# Sheet1.net
KiCad netlist of a schematic drawn in Altium Designer
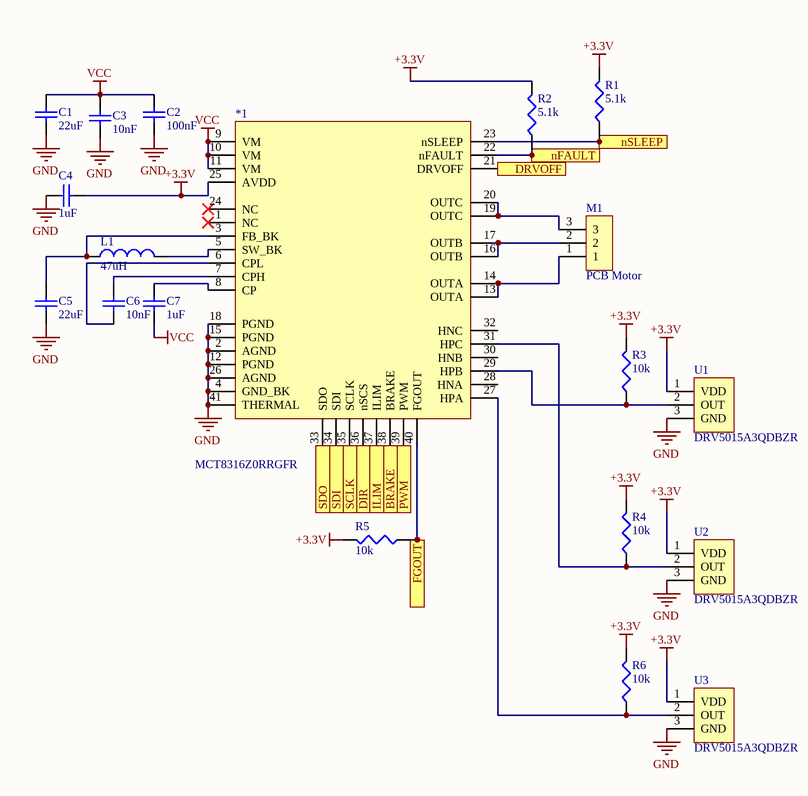
[diagram p0: Sheet1.SchDoc]

(export (version "E")
  (design (tool "Eeschema 10.0.6"))
  (components
    (comp (ref "*1")
      (value "MCT8316Z0RRGFR")
      (footprint "MCF8315A")
      (libsource (lib "Carl Bugeja's Library") (part "MCF8315A"))
    )
    (comp (ref "C1")
      (value "22uF")
      (footprint "CAPC1005X56X25ML10T15")
      (description "'LMK105BJ225MV-F")
      (fields
        (field (name "MANUFACTURER") "AVX Interconnect / Elco")
        (field (name "PART NUMBER") "0402YC104KAT2A")
      )
      (libsource (lib "Altium Content Vault") (part "CAP"))
    )
    (comp (ref "C2")
      (value "100nF")
      (footprint "CAPC1005X56X25ML10T15")
      (description "'04025C103MAT2A")
      (fields
        (field (name "MANUFACTURER") "AVX Interconnect / Elco")
        (field (name "PART NUMBER") "0402YC103MAT2A")
      )
      (libsource (lib "Altium Content Vault") (part "CAP"))
    )
    (comp (ref "C3")
      (value "10nF")
      (footprint "CAPC1005X56X25ML10T15")
      (description "'04025C103MAT2A")
      (fields
        (field (name "MANUFACTURER") "AVX Interconnect / Elco")
        (field (name "PART NUMBER") "0402YC103MAT2A")
      )
      (libsource (lib "Altium Content Vault") (part "CAP"))
    )
    (comp (ref "C4")
      (value "1uF")
      (footprint "CAPC1005X56X25ML10T15")
      (description "'04025C103MAT2A")
      (fields
        (field (name "MANUFACTURER") "AVX Interconnect / Elco")
        (field (name "PART NUMBER") "0402YC103MAT2A")
      )
      (libsource (lib "Altium Content Vault") (part "CAP"))
    )
    (comp (ref "C5")
      (value "22uF")
      (footprint "CAPC1005X56X25ML10T15")
      (description "'04025C103MAT2A")
      (fields
        (field (name "MANUFACTURER") "AVX Interconnect / Elco")
        (field (name "PART NUMBER") "0402YC103MAT2A")
      )
      (libsource (lib "Altium Content Vault") (part "CAP"))
    )
    (comp (ref "C6")
      (value "10nF")
      (footprint "CAPC1005X56X25ML10T15")
      (description "'04025C103MAT2A")
      (fields
        (field (name "MANUFACTURER") "AVX Interconnect / Elco")
        (field (name "PART NUMBER") "0402YC103MAT2A")
      )
      (libsource (lib "Altium Content Vault") (part "CAP"))
    )
    (comp (ref "C7")
      (value "1uF")
      (footprint "CAPC1005X56X25ML10T15")
      (description "'04025C103MAT2A")
      (fields
        (field (name "MANUFACTURER") "AVX Interconnect / Elco")
        (field (name "PART NUMBER") "0402YC103MAT2A")
      )
      (libsource (lib "Altium Content Vault") (part "CAP"))
    )
    (comp (ref "L1")
      (value "47uH")
      (footprint "RESC0603X02N")
      (libsource (lib "Carl Bugeja's Library") (part "IND"))
    )
    (comp (ref "M1")
      (value "PCB Motor")
      (footprint "PCB Motor 6Sv5")
      (libsource (lib "Carl Bugeja's Library") (part "PCB Motor"))
    )
    (comp (ref "R1")
      (value "5.1k")
      (footprint "RESC1005X03N")
      (libsource (lib "Compact_Schlib") (part "RES"))
    )
    (comp (ref "R2")
      (value "5.1k")
      (footprint "RESC1005X03N")
      (libsource (lib "Compact_Schlib") (part "RES"))
    )
    (comp (ref "R3") (value "10k") (footprint "RESC1005X03N") (libsource (lib "Compact_Schlib") (part "RES")))
    (comp (ref "R4") (value "10k") (footprint "RESC1005X03N") (libsource (lib "Compact_Schlib") (part "RES")))
    (comp (ref "R5") (value "10k") (footprint "RESC1005X03N") (libsource (lib "Compact_Schlib") (part "RES")))
    (comp (ref "R6") (value "10k") (footprint "RESC1005X03N") (libsource (lib "Compact_Schlib") (part "RES")))
    (comp (ref "U1")
      (value "DRV5015A3QDBZR")
      (footprint "SOT95P237X95-3N")
      (libsource (lib "Carl Bugeja's Library") (part "DRV5015A3QDBZR"))
    )
    (comp (ref "U2")
      (value "DRV5015A3QDBZR")
      (footprint "SOT95P237X95-3N")
      (libsource (lib "Carl Bugeja's Library") (part "DRV5015A3QDBZR"))
    )
    (comp (ref "U3")
      (value "DRV5015A3QDBZR")
      (footprint "SOT95P237X95-3N")
      (libsource (lib "Carl Bugeja's Library") (part "DRV5015A3QDBZR"))
    )
  )
  (nets
    (net (code "1") (name "+3.3V") (class "Default")
      (node (ref "*1") (pin "25") (pinfunction "AVDD_25") (pintype "passive"))
      (node (ref "C4") (pin "2") (pinfunction "2_2") (pintype "passive"))
      (node (ref "R1") (pin "2") (pinfunction "2_2") (pintype "passive"))
      (node (ref "R2") (pin "2") (pinfunction "2_2") (pintype "passive"))
      (node (ref "R3") (pin "2") (pinfunction "2_2") (pintype "passive"))
      (node (ref "R4") (pin "2") (pinfunction "2_2") (pintype "passive"))
      (node (ref "R5") (pin "2") (pinfunction "2_2") (pintype "passive"))
      (node (ref "R6") (pin "2") (pinfunction "2_2") (pintype "passive"))
      (node (ref "U1") (pin "1") (pinfunction "VDD_1") (pintype "passive"))
      (node (ref "U2") (pin "1") (pinfunction "VDD_1") (pintype "passive"))
      (node (ref "U3") (pin "1") (pinfunction "VDD_1") (pintype "passive"))
    )
    (net (code "2") (name "/BRAKE") (class "Default")
      (node (ref "*1") (pin "38") (pinfunction "BRAKE_38") (pintype "passive"))
    )
    (net (code "3") (name "/DIR") (class "Default")
      (node (ref "*1") (pin "36") (pinfunction "nSCS_36") (pintype "passive"))
    )
    (net (code "4") (name "/DRVOFF") (class "Default")
      (node (ref "*1") (pin "21") (pinfunction "DRVOFF_21") (pintype "passive"))
    )
    (net (code "5") (name "/FGOUT") (class "Default")
      (node (ref "*1") (pin "40") (pinfunction "FGOUT_40") (pintype "passive"))
      (node (ref "R5") (pin "1") (pinfunction "1_1") (pintype "passive"))
    )
    (net (code "6") (name "/ILIM") (class "Default")
      (node (ref "*1") (pin "37") (pinfunction "ILIM_37") (pintype "passive"))
    )
    (net (code "7") (name "/PWM") (class "Default")
      (node (ref "*1") (pin "39") (pinfunction "PWM_39") (pintype "passive"))
    )
    (net (code "8") (name "/SCLK") (class "Default")
      (node (ref "*1") (pin "35") (pinfunction "SCLK_35") (pintype "passive"))
    )
    (net (code "9") (name "/SDI") (class "Default")
      (node (ref "*1") (pin "34") (pinfunction "SDI_34") (pintype "passive"))
    )
    (net (code "10") (name "/SDO") (class "Default")
      (node (ref "*1") (pin "33") (pinfunction "SDO_33") (pintype "passive"))
    )
    (net (code "11") (name "/nFAULT") (class "Default")
      (node (ref "*1") (pin "22") (pinfunction "nFAULT_22") (pintype "passive"))
      (node (ref "R2") (pin "1") (pinfunction "1_1") (pintype "passive"))
    )
    (net (code "12") (name "/nSLEEP") (class "Default")
      (node (ref "*1") (pin "23") (pinfunction "nSLEEP_23") (pintype "passive"))
      (node (ref "R1") (pin "1") (pinfunction "1_1") (pintype "passive"))
    )
    (net (code "13") (name "GND") (class "Default")
      (node (ref "*1") (pin "12") (pinfunction "PGND_12") (pintype "passive"))
      (node (ref "*1") (pin "15") (pinfunction "PGND_15") (pintype "passive"))
      (node (ref "*1") (pin "18") (pinfunction "PGND_18") (pintype "passive"))
      (node (ref "*1") (pin "2") (pinfunction "AGND_2") (pintype "passive"))
      (node (ref "*1") (pin "26") (pinfunction "AGND_26") (pintype "passive"))
      (node (ref "*1") (pin "4") (pinfunction "GND_BK_4") (pintype "passive"))
      (node (ref "*1") (pin "41") (pinfunction "THERMAL_41") (pintype "passive"))
      (node (ref "C1") (pin "1") (pinfunction "1_1") (pintype "passive"))
      (node (ref "C2") (pin "1") (pinfunction "1_1") (pintype "passive"))
      (node (ref "C3") (pin "1") (pinfunction "1_1") (pintype "passive"))
      (node (ref "C4") (pin "1") (pinfunction "1_1") (pintype "passive"))
      (node (ref "C5") (pin "2") (pinfunction "2_2") (pintype "passive"))
      (node (ref "U1") (pin "3") (pinfunction "GND_3") (pintype "passive"))
      (node (ref "U2") (pin "3") (pinfunction "GND_3") (pintype "passive"))
      (node (ref "U3") (pin "3") (pinfunction "GND_3") (pintype "passive"))
    )
    (net (code "14") (name "Net-(*1-CP)") (class "Default")
      (node (ref "*1") (pin "8") (pinfunction "CP_8") (pintype "passive"))
      (node (ref "C7") (pin "1") (pinfunction "1_1") (pintype "passive"))
    )
    (net (code "15") (name "Net-(*1-CPH)") (class "Default")
      (node (ref "*1") (pin "7") (pinfunction "CPH_7") (pintype "passive"))
      (node (ref "C6") (pin "1") (pinfunction "1_1") (pintype "passive"))
    )
    (net (code "16") (name "Net-(*1-CPL)") (class "Default")
      (node (ref "*1") (pin "6") (pinfunction "CPL_6") (pintype "passive"))
      (node (ref "C6") (pin "2") (pinfunction "2_2") (pintype "passive"))
    )
    (net (code "17") (name "Net-(*1-FB_BK)") (class "Default")
      (node (ref "*1") (pin "3") (pinfunction "FB_BK_3") (pintype "passive"))
      (node (ref "C5") (pin "1") (pinfunction "1_1") (pintype "passive"))
      (node (ref "L1") (pin "1") (pinfunction "1_1") (pintype "passive"))
    )
    (net (code "18") (name "Net-(*1-HPA)") (class "Default")
      (node (ref "*1") (pin "27") (pinfunction "HPA_27") (pintype "passive"))
      (node (ref "R6") (pin "1") (pinfunction "1_1") (pintype "passive"))
      (node (ref "U3") (pin "2") (pinfunction "OUT_2") (pintype "passive"))
    )
    (net (code "19") (name "Net-(*1-HPB)") (class "Default")
      (node (ref "*1") (pin "29") (pinfunction "HPB_29") (pintype "passive"))
      (node (ref "R3") (pin "1") (pinfunction "1_1") (pintype "passive"))
      (node (ref "U1") (pin "2") (pinfunction "OUT_2") (pintype "passive"))
    )
    (net (code "20") (name "Net-(*1-HPC)") (class "Default")
      (node (ref "*1") (pin "31") (pinfunction "HPC_31") (pintype "passive"))
      (node (ref "R4") (pin "1") (pinfunction "1_1") (pintype "passive"))
      (node (ref "U2") (pin "2") (pinfunction "OUT_2") (pintype "passive"))
    )
    (net (code "21") (name "Net-(*1-OUTA-Pad13)") (class "Default")
      (node (ref "*1") (pin "13") (pinfunction "OUTA_13") (pintype "passive"))
      (node (ref "*1") (pin "14") (pinfunction "OUTA_14") (pintype "passive"))
      (node (ref "M1") (pin "1") (pinfunction "1_1") (pintype "passive"))
    )
    (net (code "22") (name "Net-(*1-OUTB-Pad16)") (class "Default")
      (node (ref "*1") (pin "16") (pinfunction "OUTB_16") (pintype "passive"))
      (node (ref "*1") (pin "17") (pinfunction "OUTB_17") (pintype "passive"))
      (node (ref "M1") (pin "2") (pinfunction "2_2") (pintype "passive"))
    )
    (net (code "23") (name "Net-(*1-OUTC-Pad19)") (class "Default")
      (node (ref "*1") (pin "19") (pinfunction "OUTC_19") (pintype "passive"))
      (node (ref "*1") (pin "20") (pinfunction "OUTC_20") (pintype "passive"))
      (node (ref "M1") (pin "3") (pinfunction "3_3") (pintype "passive"))
    )
    (net (code "24") (name "Net-(*1-SW_BK)") (class "Default")
      (node (ref "*1") (pin "5") (pinfunction "SW_BK_5") (pintype "passive"))
      (node (ref "L1") (pin "2") (pinfunction "2_2") (pintype "passive"))
    )
    (net (code "25") (name "VCC") (class "Default")
      (node (ref "*1") (pin "10") (pinfunction "VM_10") (pintype "passive"))
      (node (ref "*1") (pin "11") (pinfunction "VM_11") (pintype "passive"))
      (node (ref "*1") (pin "9") (pinfunction "VM_9") (pintype "passive"))
      (node (ref "C1") (pin "2") (pinfunction "2_2") (pintype "passive"))
      (node (ref "C2") (pin "2") (pinfunction "2_2") (pintype "passive"))
      (node (ref "C3") (pin "2") (pinfunction "2_2") (pintype "passive"))
      (node (ref "C7") (pin "2") (pinfunction "2_2") (pintype "passive"))
    )
    (net (code "26") (name "unconnected-(*1-HNA-Pad28)") (class "Default")
      (node (ref "*1") (pin "28") (pinfunction "HNA_28") (pintype "passive"))
    )
    (net (code "27") (name "unconnected-(*1-HNB-Pad30)") (class "Default")
      (node (ref "*1") (pin "30") (pinfunction "HNB_30") (pintype "passive"))
    )
    (net (code "28") (name "unconnected-(*1-HNC-Pad32)") (class "Default")
      (node (ref "*1") (pin "32") (pinfunction "HNC_32") (pintype "passive"))
    )
    (net (code "29") (name "unconnected-(*1-NC-Pad1)") (class "Default")
      (node (ref "*1") (pin "1") (pinfunction "NC_1") (pintype "passive+no_connect"))
    )
    (net (code "30") (name "unconnected-(*1-NC-Pad24)") (class "Default")
      (node (ref "*1") (pin "24") (pinfunction "NC_24") (pintype "passive+no_connect"))
    )
  )
)
